# CON_RS232DCE_DB9.net
KiCad netlist of a schematic drawn in Altium Designer
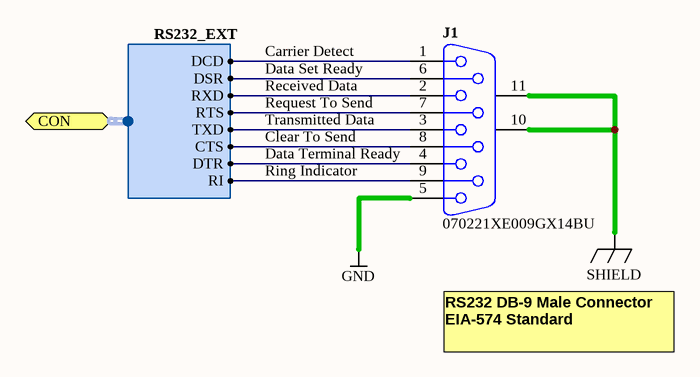
[diagram p0: CON_RS232DCE_DB9.SchDoc]

(export (version "E")
  (design (tool "Eeschema 10.0.6"))
  (components
    (comp (ref "J1")
      (value "070221XE009GX14BU")
      (footprint "070221XE009GX14BU")
      (description "Connector DB9 SMD Male/Pins; SUYIN")
      (libsource (lib "AltiumDesignLibrary") (part "CON-DB-9-M-RA"))
    )
  )
  (nets
    (net (code "2") (name "/CTS") (class "Default")
      (node (ref "J1") (pin "8") (pinfunction "8_8") (pintype "passive"))
    )
    (net (code "3") (name "/DCD") (class "Default")
      (node (ref "J1") (pin "1") (pinfunction "1_1") (pintype "passive"))
    )
    (net (code "4") (name "/DSR") (class "Default")
      (node (ref "J1") (pin "6") (pinfunction "6_6") (pintype "passive"))
    )
    (net (code "5") (name "/DTR") (class "Default")
      (node (ref "J1") (pin "4") (pinfunction "4_4") (pintype "passive"))
    )
    (net (code "6") (name "/RI") (class "Default")
      (node (ref "J1") (pin "9") (pinfunction "9_9") (pintype "passive"))
    )
    (net (code "7") (name "/RTS") (class "Default")
      (node (ref "J1") (pin "7") (pinfunction "7_7") (pintype "passive"))
    )
    (net (code "8") (name "/RXD") (class "Default")
      (node (ref "J1") (pin "2") (pinfunction "2_2") (pintype "passive"))
    )
    (net (code "9") (name "/TXD") (class "Default")
      (node (ref "J1") (pin "3") (pinfunction "3_3") (pintype "passive"))
    )
    (net (code "11") (name "GND") (class "Default")
      (node (ref "J1") (pin "5") (pinfunction "5_5") (pintype "passive"))
    )
    (net (code "12") (name "SHIELD") (class "Default")
      (node (ref "J1") (pin "10") (pinfunction "MH1_10") (pintype "passive"))
      (node (ref "J1") (pin "11") (pinfunction "MH2_11") (pintype "passive"))
    )
  )
)
